# main.net
KiCad netlist of a schematic drawn in EAGLE
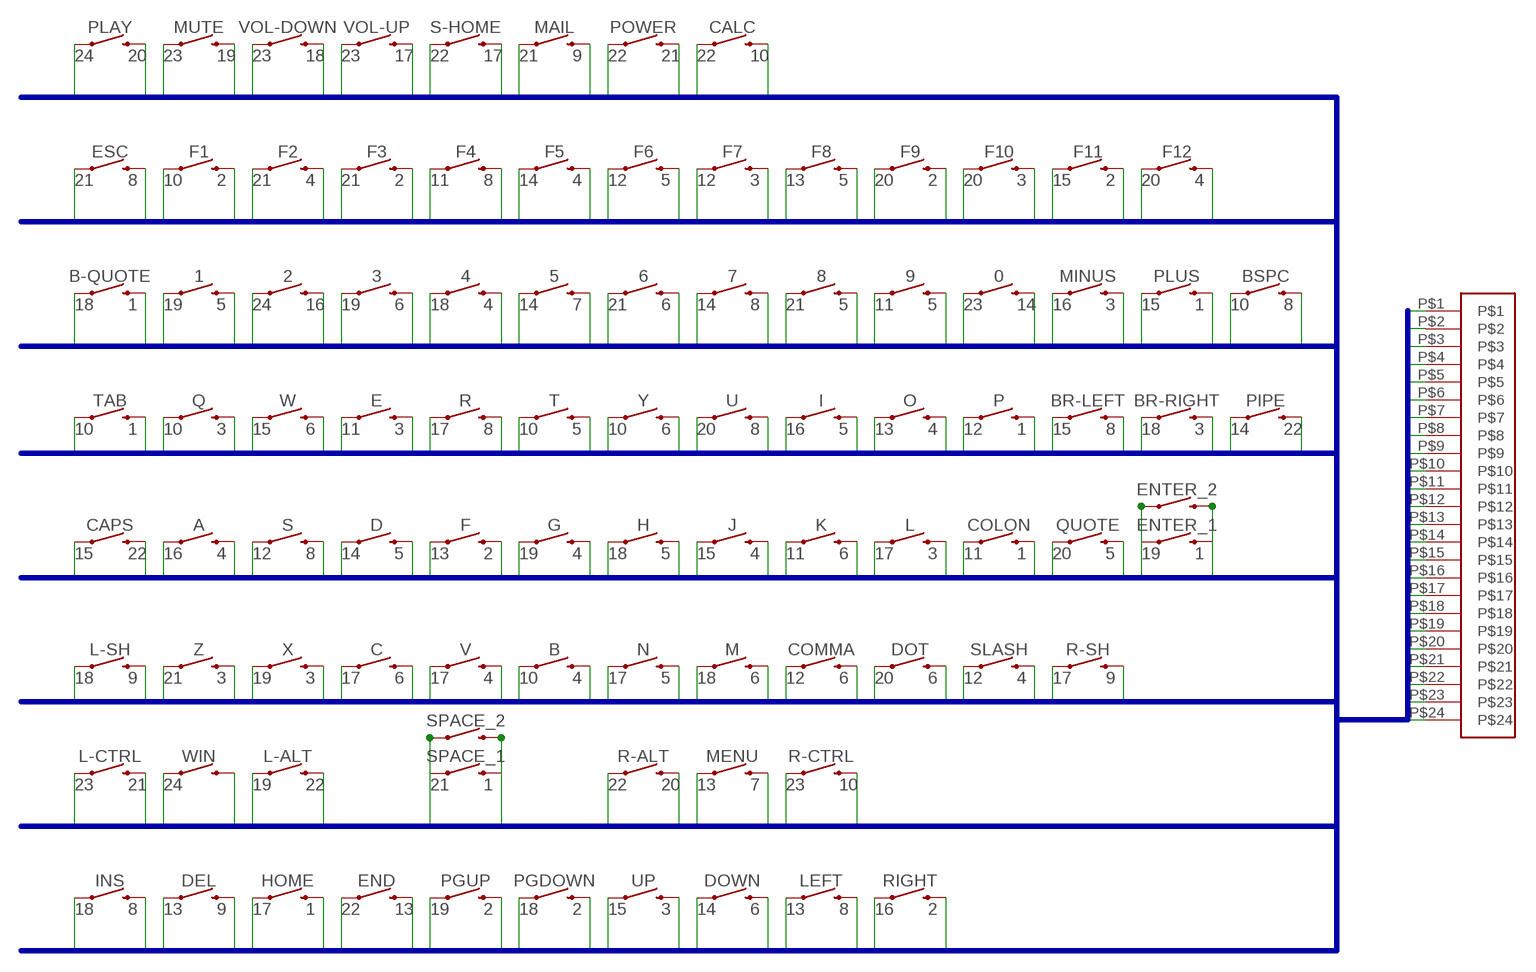
[diagram p0: schematic, sheet 1]

(export (version "E")
  (design (tool "Eeschema 10.0.6"))
  (components
    (comp (ref "0")
      (value "MOMENTARY-SWITCH-SPST-SMD-5.2MM-TALL")
      (footprint "eagle-import:TACTILE_SWITCH_SMD_5.2MM")
      (libsource (lib "eagle-import") (part "MOMENTARY-SWITCH-SPST-SMD-5.2MM-TALL"))
    )
    (comp (ref "1")
      (value "MOMENTARY-SWITCH-SPST-SMD-5.2MM-TALL")
      (footprint "eagle-import:TACTILE_SWITCH_SMD_5.2MM")
      (libsource (lib "eagle-import") (part "MOMENTARY-SWITCH-SPST-SMD-5.2MM-TALL"))
    )
    (comp (ref "2")
      (value "MOMENTARY-SWITCH-SPST-SMD-5.2MM-TALL")
      (footprint "eagle-import:TACTILE_SWITCH_SMD_5.2MM")
      (libsource (lib "eagle-import") (part "MOMENTARY-SWITCH-SPST-SMD-5.2MM-TALL"))
    )
    (comp (ref "3")
      (value "MOMENTARY-SWITCH-SPST-SMD-5.2MM-TALL")
      (footprint "eagle-import:TACTILE_SWITCH_SMD_5.2MM")
      (libsource (lib "eagle-import") (part "MOMENTARY-SWITCH-SPST-SMD-5.2MM-TALL"))
    )
    (comp (ref "4")
      (value "MOMENTARY-SWITCH-SPST-SMD-5.2MM-TALL")
      (footprint "eagle-import:TACTILE_SWITCH_SMD_5.2MM")
      (libsource (lib "eagle-import") (part "MOMENTARY-SWITCH-SPST-SMD-5.2MM-TALL"))
    )
    (comp (ref "5")
      (value "MOMENTARY-SWITCH-SPST-SMD-5.2MM-TALL")
      (footprint "eagle-import:TACTILE_SWITCH_SMD_5.2MM")
      (libsource (lib "eagle-import") (part "MOMENTARY-SWITCH-SPST-SMD-5.2MM-TALL"))
    )
    (comp (ref "6")
      (value "MOMENTARY-SWITCH-SPST-SMD-5.2MM-TALL")
      (footprint "eagle-import:TACTILE_SWITCH_SMD_5.2MM")
      (libsource (lib "eagle-import") (part "MOMENTARY-SWITCH-SPST-SMD-5.2MM-TALL"))
    )
    (comp (ref "7")
      (value "MOMENTARY-SWITCH-SPST-SMD-5.2MM-TALL")
      (footprint "eagle-import:TACTILE_SWITCH_SMD_5.2MM")
      (libsource (lib "eagle-import") (part "MOMENTARY-SWITCH-SPST-SMD-5.2MM-TALL"))
    )
    (comp (ref "8")
      (value "MOMENTARY-SWITCH-SPST-SMD-5.2MM-TALL")
      (footprint "eagle-import:TACTILE_SWITCH_SMD_5.2MM")
      (libsource (lib "eagle-import") (part "MOMENTARY-SWITCH-SPST-SMD-5.2MM-TALL"))
    )
    (comp (ref "9")
      (value "MOMENTARY-SWITCH-SPST-SMD-5.2MM-TALL")
      (footprint "eagle-import:TACTILE_SWITCH_SMD_5.2MM")
      (libsource (lib "eagle-import") (part "MOMENTARY-SWITCH-SPST-SMD-5.2MM-TALL"))
    )
    (comp (ref "A")
      (value "MOMENTARY-SWITCH-SPST-SMD-5.2MM-TALL")
      (footprint "eagle-import:TACTILE_SWITCH_SMD_5.2MM")
      (libsource (lib "eagle-import") (part "MOMENTARY-SWITCH-SPST-SMD-5.2MM-TALL"))
    )
    (comp (ref "B")
      (value "MOMENTARY-SWITCH-SPST-SMD-5.2MM-TALL")
      (footprint "eagle-import:TACTILE_SWITCH_SMD_5.2MM")
      (libsource (lib "eagle-import") (part "MOMENTARY-SWITCH-SPST-SMD-5.2MM-TALL"))
    )
    (comp (ref "B-QUOTE")
      (value "MOMENTARY-SWITCH-SPST-SMD-5.2MM-TALL")
      (footprint "eagle-import:TACTILE_SWITCH_SMD_5.2MM")
      (libsource (lib "eagle-import") (part "MOMENTARY-SWITCH-SPST-SMD-5.2MM-TALL"))
    )
    (comp (ref "BR-LEFT")
      (value "MOMENTARY-SWITCH-SPST-SMD-5.2MM-TALL")
      (footprint "eagle-import:TACTILE_SWITCH_SMD_5.2MM")
      (libsource (lib "eagle-import") (part "MOMENTARY-SWITCH-SPST-SMD-5.2MM-TALL"))
    )
    (comp (ref "BR-RIGHT")
      (value "MOMENTARY-SWITCH-SPST-SMD-5.2MM-TALL")
      (footprint "eagle-import:TACTILE_SWITCH_SMD_5.2MM")
      (libsource (lib "eagle-import") (part "MOMENTARY-SWITCH-SPST-SMD-5.2MM-TALL"))
    )
    (comp (ref "BSPC")
      (value "MOMENTARY-SWITCH-SPST-SMD-5.2MM-TALL")
      (footprint "eagle-import:TACTILE_SWITCH_SMD_5.2MM")
      (libsource (lib "eagle-import") (part "MOMENTARY-SWITCH-SPST-SMD-5.2MM-TALL"))
    )
    (comp (ref "C")
      (value "MOMENTARY-SWITCH-SPST-SMD-5.2MM-TALL")
      (footprint "eagle-import:TACTILE_SWITCH_SMD_5.2MM")
      (libsource (lib "eagle-import") (part "MOMENTARY-SWITCH-SPST-SMD-5.2MM-TALL"))
    )
    (comp (ref "CALC")
      (value "MOMENTARY-SWITCH-SPST-SMD-5.2MM-TALL")
      (footprint "eagle-import:TACTILE_SWITCH_SMD_5.2MM")
      (libsource (lib "eagle-import") (part "MOMENTARY-SWITCH-SPST-SMD-5.2MM-TALL"))
    )
    (comp (ref "CAPS")
      (value "MOMENTARY-SWITCH-SPST-SMD-5.2MM-TALL")
      (footprint "eagle-import:TACTILE_SWITCH_SMD_5.2MM")
      (libsource (lib "eagle-import") (part "MOMENTARY-SWITCH-SPST-SMD-5.2MM-TALL"))
    )
    (comp (ref "COLON")
      (value "MOMENTARY-SWITCH-SPST-SMD-5.2MM-TALL")
      (footprint "eagle-import:TACTILE_SWITCH_SMD_5.2MM")
      (libsource (lib "eagle-import") (part "MOMENTARY-SWITCH-SPST-SMD-5.2MM-TALL"))
    )
    (comp (ref "COMMA")
      (value "MOMENTARY-SWITCH-SPST-SMD-5.2MM-TALL")
      (footprint "eagle-import:TACTILE_SWITCH_SMD_5.2MM")
      (libsource (lib "eagle-import") (part "MOMENTARY-SWITCH-SPST-SMD-5.2MM-TALL"))
    )
    (comp (ref "D")
      (value "MOMENTARY-SWITCH-SPST-SMD-5.2MM-TALL")
      (footprint "eagle-import:TACTILE_SWITCH_SMD_5.2MM")
      (libsource (lib "eagle-import") (part "MOMENTARY-SWITCH-SPST-SMD-5.2MM-TALL"))
    )
    (comp (ref "DEL")
      (value "MOMENTARY-SWITCH-SPST-SMD-5.2MM-TALL")
      (footprint "eagle-import:TACTILE_SWITCH_SMD_5.2MM")
      (libsource (lib "eagle-import") (part "MOMENTARY-SWITCH-SPST-SMD-5.2MM-TALL"))
    )
    (comp (ref "DOT")
      (value "MOMENTARY-SWITCH-SPST-SMD-5.2MM-TALL")
      (footprint "eagle-import:TACTILE_SWITCH_SMD_5.2MM")
      (libsource (lib "eagle-import") (part "MOMENTARY-SWITCH-SPST-SMD-5.2MM-TALL"))
    )
    (comp (ref "DOWN")
      (value "MOMENTARY-SWITCH-SPST-SMD-5.2MM-TALL")
      (footprint "eagle-import:TACTILE_SWITCH_SMD_5.2MM")
      (libsource (lib "eagle-import") (part "MOMENTARY-SWITCH-SPST-SMD-5.2MM-TALL"))
    )
    (comp (ref "E")
      (value "MOMENTARY-SWITCH-SPST-SMD-5.2MM-TALL")
      (footprint "eagle-import:TACTILE_SWITCH_SMD_5.2MM")
      (libsource (lib "eagle-import") (part "MOMENTARY-SWITCH-SPST-SMD-5.2MM-TALL"))
    )
    (comp (ref "END")
      (value "MOMENTARY-SWITCH-SPST-SMD-5.2MM-TALL")
      (footprint "eagle-import:TACTILE_SWITCH_SMD_5.2MM")
      (libsource (lib "eagle-import") (part "MOMENTARY-SWITCH-SPST-SMD-5.2MM-TALL"))
    )
    (comp (ref "ENTER_1")
      (value "MOMENTARY-SWITCH-SPST-SMD-5.2MM-TALL")
      (footprint "eagle-import:TACTILE_SWITCH_SMD_5.2MM")
      (libsource (lib "eagle-import") (part "MOMENTARY-SWITCH-SPST-SMD-5.2MM-TALL"))
    )
    (comp (ref "ENTER_2")
      (value "MOMENTARY-SWITCH-SPST-SMD-5.2MM-TALL")
      (footprint "eagle-import:TACTILE_SWITCH_SMD_5.2MM")
      (libsource (lib "eagle-import") (part "MOMENTARY-SWITCH-SPST-SMD-5.2MM-TALL"))
    )
    (comp (ref "ESC")
      (value "MOMENTARY-SWITCH-SPST-SMD-5.2MM-TALL")
      (footprint "eagle-import:TACTILE_SWITCH_SMD_5.2MM")
      (libsource (lib "eagle-import") (part "MOMENTARY-SWITCH-SPST-SMD-5.2MM-TALL"))
    )
    (comp (ref "F")
      (value "MOMENTARY-SWITCH-SPST-SMD-5.2MM-TALL")
      (footprint "eagle-import:TACTILE_SWITCH_SMD_5.2MM")
      (libsource (lib "eagle-import") (part "MOMENTARY-SWITCH-SPST-SMD-5.2MM-TALL"))
    )
    (comp (ref "F1")
      (value "MOMENTARY-SWITCH-SPST-SMD-5.2MM-TALL")
      (footprint "eagle-import:TACTILE_SWITCH_SMD_5.2MM")
      (libsource (lib "eagle-import") (part "MOMENTARY-SWITCH-SPST-SMD-5.2MM-TALL"))
    )
    (comp (ref "F2")
      (value "MOMENTARY-SWITCH-SPST-SMD-5.2MM-TALL")
      (footprint "eagle-import:TACTILE_SWITCH_SMD_5.2MM")
      (libsource (lib "eagle-import") (part "MOMENTARY-SWITCH-SPST-SMD-5.2MM-TALL"))
    )
    (comp (ref "F3")
      (value "MOMENTARY-SWITCH-SPST-SMD-5.2MM-TALL")
      (footprint "eagle-import:TACTILE_SWITCH_SMD_5.2MM")
      (libsource (lib "eagle-import") (part "MOMENTARY-SWITCH-SPST-SMD-5.2MM-TALL"))
    )
    (comp (ref "F4")
      (value "MOMENTARY-SWITCH-SPST-SMD-5.2MM-TALL")
      (footprint "eagle-import:TACTILE_SWITCH_SMD_5.2MM")
      (libsource (lib "eagle-import") (part "MOMENTARY-SWITCH-SPST-SMD-5.2MM-TALL"))
    )
    (comp (ref "F5")
      (value "MOMENTARY-SWITCH-SPST-SMD-5.2MM-TALL")
      (footprint "eagle-import:TACTILE_SWITCH_SMD_5.2MM")
      (libsource (lib "eagle-import") (part "MOMENTARY-SWITCH-SPST-SMD-5.2MM-TALL"))
    )
    (comp (ref "F6")
      (value "MOMENTARY-SWITCH-SPST-SMD-5.2MM-TALL")
      (footprint "eagle-import:TACTILE_SWITCH_SMD_5.2MM")
      (libsource (lib "eagle-import") (part "MOMENTARY-SWITCH-SPST-SMD-5.2MM-TALL"))
    )
    (comp (ref "F7")
      (value "MOMENTARY-SWITCH-SPST-SMD-5.2MM-TALL")
      (footprint "eagle-import:TACTILE_SWITCH_SMD_5.2MM")
      (libsource (lib "eagle-import") (part "MOMENTARY-SWITCH-SPST-SMD-5.2MM-TALL"))
    )
    (comp (ref "F8")
      (value "MOMENTARY-SWITCH-SPST-SMD-5.2MM-TALL")
      (footprint "eagle-import:TACTILE_SWITCH_SMD_5.2MM")
      (libsource (lib "eagle-import") (part "MOMENTARY-SWITCH-SPST-SMD-5.2MM-TALL"))
    )
    (comp (ref "F9")
      (value "MOMENTARY-SWITCH-SPST-SMD-5.2MM-TALL")
      (footprint "eagle-import:TACTILE_SWITCH_SMD_5.2MM")
      (libsource (lib "eagle-import") (part "MOMENTARY-SWITCH-SPST-SMD-5.2MM-TALL"))
    )
    (comp (ref "F10")
      (value "MOMENTARY-SWITCH-SPST-SMD-5.2MM-TALL")
      (footprint "eagle-import:TACTILE_SWITCH_SMD_5.2MM")
      (libsource (lib "eagle-import") (part "MOMENTARY-SWITCH-SPST-SMD-5.2MM-TALL"))
    )
    (comp (ref "F11")
      (value "MOMENTARY-SWITCH-SPST-SMD-5.2MM-TALL")
      (footprint "eagle-import:TACTILE_SWITCH_SMD_5.2MM")
      (libsource (lib "eagle-import") (part "MOMENTARY-SWITCH-SPST-SMD-5.2MM-TALL"))
    )
    (comp (ref "F12")
      (value "MOMENTARY-SWITCH-SPST-SMD-5.2MM-TALL")
      (footprint "eagle-import:TACTILE_SWITCH_SMD_5.2MM")
      (libsource (lib "eagle-import") (part "MOMENTARY-SWITCH-SPST-SMD-5.2MM-TALL"))
    )
    (comp (ref "G")
      (value "MOMENTARY-SWITCH-SPST-SMD-5.2MM-TALL")
      (footprint "eagle-import:TACTILE_SWITCH_SMD_5.2MM")
      (libsource (lib "eagle-import") (part "MOMENTARY-SWITCH-SPST-SMD-5.2MM-TALL"))
    )
    (comp (ref "H")
      (value "MOMENTARY-SWITCH-SPST-SMD-5.2MM-TALL")
      (footprint "eagle-import:TACTILE_SWITCH_SMD_5.2MM")
      (libsource (lib "eagle-import") (part "MOMENTARY-SWITCH-SPST-SMD-5.2MM-TALL"))
    )
    (comp (ref "HOME")
      (value "MOMENTARY-SWITCH-SPST-SMD-5.2MM-TALL")
      (footprint "eagle-import:TACTILE_SWITCH_SMD_5.2MM")
      (libsource (lib "eagle-import") (part "MOMENTARY-SWITCH-SPST-SMD-5.2MM-TALL"))
    )
    (comp (ref "I")
      (value "MOMENTARY-SWITCH-SPST-SMD-5.2MM-TALL")
      (footprint "eagle-import:TACTILE_SWITCH_SMD_5.2MM")
      (libsource (lib "eagle-import") (part "MOMENTARY-SWITCH-SPST-SMD-5.2MM-TALL"))
    )
    (comp (ref "INS")
      (value "MOMENTARY-SWITCH-SPST-SMD-5.2MM-TALL")
      (footprint "eagle-import:TACTILE_SWITCH_SMD_5.2MM")
      (libsource (lib "eagle-import") (part "MOMENTARY-SWITCH-SPST-SMD-5.2MM-TALL"))
    )
    (comp (ref "J")
      (value "MOMENTARY-SWITCH-SPST-SMD-5.2MM-TALL")
      (footprint "eagle-import:TACTILE_SWITCH_SMD_5.2MM")
      (libsource (lib "eagle-import") (part "MOMENTARY-SWITCH-SPST-SMD-5.2MM-TALL"))
    )
    (comp (ref "K")
      (value "MOMENTARY-SWITCH-SPST-SMD-5.2MM-TALL")
      (footprint "eagle-import:TACTILE_SWITCH_SMD_5.2MM")
      (libsource (lib "eagle-import") (part "MOMENTARY-SWITCH-SPST-SMD-5.2MM-TALL"))
    )
    (comp (ref "L")
      (value "MOMENTARY-SWITCH-SPST-SMD-5.2MM-TALL")
      (footprint "eagle-import:TACTILE_SWITCH_SMD_5.2MM")
      (libsource (lib "eagle-import") (part "MOMENTARY-SWITCH-SPST-SMD-5.2MM-TALL"))
    )
    (comp (ref "L-ALT")
      (value "MOMENTARY-SWITCH-SPST-SMD-5.2MM-TALL")
      (footprint "eagle-import:TACTILE_SWITCH_SMD_5.2MM")
      (libsource (lib "eagle-import") (part "MOMENTARY-SWITCH-SPST-SMD-5.2MM-TALL"))
    )
    (comp (ref "L-CTRL")
      (value "MOMENTARY-SWITCH-SPST-SMD-5.2MM-TALL")
      (footprint "eagle-import:TACTILE_SWITCH_SMD_5.2MM")
      (libsource (lib "eagle-import") (part "MOMENTARY-SWITCH-SPST-SMD-5.2MM-TALL"))
    )
    (comp (ref "L-SH")
      (value "MOMENTARY-SWITCH-SPST-SMD-5.2MM-TALL")
      (footprint "eagle-import:TACTILE_SWITCH_SMD_5.2MM")
      (libsource (lib "eagle-import") (part "MOMENTARY-SWITCH-SPST-SMD-5.2MM-TALL"))
    )
    (comp (ref "LEFT")
      (value "MOMENTARY-SWITCH-SPST-SMD-5.2MM-TALL")
      (footprint "eagle-import:TACTILE_SWITCH_SMD_5.2MM")
      (libsource (lib "eagle-import") (part "MOMENTARY-SWITCH-SPST-SMD-5.2MM-TALL"))
    )
    (comp (ref "M")
      (value "MOMENTARY-SWITCH-SPST-SMD-5.2MM-TALL")
      (footprint "eagle-import:TACTILE_SWITCH_SMD_5.2MM")
      (libsource (lib "eagle-import") (part "MOMENTARY-SWITCH-SPST-SMD-5.2MM-TALL"))
    )
    (comp (ref "MAIL")
      (value "MOMENTARY-SWITCH-SPST-SMD-5.2MM-TALL")
      (footprint "eagle-import:TACTILE_SWITCH_SMD_5.2MM")
      (libsource (lib "eagle-import") (part "MOMENTARY-SWITCH-SPST-SMD-5.2MM-TALL"))
    )
    (comp (ref "MENU")
      (value "MOMENTARY-SWITCH-SPST-SMD-5.2MM-TALL")
      (footprint "eagle-import:TACTILE_SWITCH_SMD_5.2MM")
      (libsource (lib "eagle-import") (part "MOMENTARY-SWITCH-SPST-SMD-5.2MM-TALL"))
    )
    (comp (ref "MINUS")
      (value "MOMENTARY-SWITCH-SPST-SMD-5.2MM-TALL")
      (footprint "eagle-import:TACTILE_SWITCH_SMD_5.2MM")
      (libsource (lib "eagle-import") (part "MOMENTARY-SWITCH-SPST-SMD-5.2MM-TALL"))
    )
    (comp (ref "MUTE")
      (value "MOMENTARY-SWITCH-SPST-SMD-5.2MM-TALL")
      (footprint "eagle-import:TACTILE_SWITCH_SMD_5.2MM")
      (libsource (lib "eagle-import") (part "MOMENTARY-SWITCH-SPST-SMD-5.2MM-TALL"))
    )
    (comp (ref "N")
      (value "MOMENTARY-SWITCH-SPST-SMD-5.2MM-TALL")
      (footprint "eagle-import:TACTILE_SWITCH_SMD_5.2MM")
      (libsource (lib "eagle-import") (part "MOMENTARY-SWITCH-SPST-SMD-5.2MM-TALL"))
    )
    (comp (ref "O")
      (value "MOMENTARY-SWITCH-SPST-SMD-5.2MM-TALL")
      (footprint "eagle-import:TACTILE_SWITCH_SMD_5.2MM")
      (libsource (lib "eagle-import") (part "MOMENTARY-SWITCH-SPST-SMD-5.2MM-TALL"))
    )
    (comp (ref "P")
      (value "MOMENTARY-SWITCH-SPST-SMD-5.2MM-TALL")
      (footprint "eagle-import:TACTILE_SWITCH_SMD_5.2MM")
      (libsource (lib "eagle-import") (part "MOMENTARY-SWITCH-SPST-SMD-5.2MM-TALL"))
    )
    (comp (ref "PGDOWN")
      (value "MOMENTARY-SWITCH-SPST-SMD-5.2MM-TALL")
      (footprint "eagle-import:TACTILE_SWITCH_SMD_5.2MM")
      (libsource (lib "eagle-import") (part "MOMENTARY-SWITCH-SPST-SMD-5.2MM-TALL"))
    )
    (comp (ref "PGUP")
      (value "MOMENTARY-SWITCH-SPST-SMD-5.2MM-TALL")
      (footprint "eagle-import:TACTILE_SWITCH_SMD_5.2MM")
      (libsource (lib "eagle-import") (part "MOMENTARY-SWITCH-SPST-SMD-5.2MM-TALL"))
    )
    (comp (ref "PIPE")
      (value "MOMENTARY-SWITCH-SPST-SMD-5.2MM-TALL")
      (footprint "eagle-import:TACTILE_SWITCH_SMD_5.2MM")
      (libsource (lib "eagle-import") (part "MOMENTARY-SWITCH-SPST-SMD-5.2MM-TALL"))
    )
    (comp (ref "PLAY")
      (value "MOMENTARY-SWITCH-SPST-SMD-5.2MM-TALL")
      (footprint "eagle-import:TACTILE_SWITCH_SMD_5.2MM")
      (libsource (lib "eagle-import") (part "MOMENTARY-SWITCH-SPST-SMD-5.2MM-TALL"))
    )
    (comp (ref "PLUS")
      (value "MOMENTARY-SWITCH-SPST-SMD-5.2MM-TALL")
      (footprint "eagle-import:TACTILE_SWITCH_SMD_5.2MM")
      (libsource (lib "eagle-import") (part "MOMENTARY-SWITCH-SPST-SMD-5.2MM-TALL"))
    )
    (comp (ref "POWER")
      (value "MOMENTARY-SWITCH-SPST-SMD-5.2MM-TALL")
      (footprint "eagle-import:TACTILE_SWITCH_SMD_5.2MM")
      (libsource (lib "eagle-import") (part "MOMENTARY-SWITCH-SPST-SMD-5.2MM-TALL"))
    )
    (comp (ref "Q")
      (value "MOMENTARY-SWITCH-SPST-SMD-5.2MM-TALL")
      (footprint "eagle-import:TACTILE_SWITCH_SMD_5.2MM")
      (libsource (lib "eagle-import") (part "MOMENTARY-SWITCH-SPST-SMD-5.2MM-TALL"))
    )
    (comp (ref "QUOTE")
      (value "MOMENTARY-SWITCH-SPST-SMD-5.2MM-TALL")
      (footprint "eagle-import:TACTILE_SWITCH_SMD_5.2MM")
      (libsource (lib "eagle-import") (part "MOMENTARY-SWITCH-SPST-SMD-5.2MM-TALL"))
    )
    (comp (ref "R")
      (value "MOMENTARY-SWITCH-SPST-SMD-5.2MM-TALL")
      (footprint "eagle-import:TACTILE_SWITCH_SMD_5.2MM")
      (libsource (lib "eagle-import") (part "MOMENTARY-SWITCH-SPST-SMD-5.2MM-TALL"))
    )
    (comp (ref "R-ALT")
      (value "MOMENTARY-SWITCH-SPST-SMD-5.2MM-TALL")
      (footprint "eagle-import:TACTILE_SWITCH_SMD_5.2MM")
      (libsource (lib "eagle-import") (part "MOMENTARY-SWITCH-SPST-SMD-5.2MM-TALL"))
    )
    (comp (ref "R-CTRL")
      (value "MOMENTARY-SWITCH-SPST-SMD-5.2MM-TALL")
      (footprint "eagle-import:TACTILE_SWITCH_SMD_5.2MM")
      (libsource (lib "eagle-import") (part "MOMENTARY-SWITCH-SPST-SMD-5.2MM-TALL"))
    )
    (comp (ref "R-SH")
      (value "MOMENTARY-SWITCH-SPST-SMD-5.2MM-TALL")
      (footprint "eagle-import:TACTILE_SWITCH_SMD_5.2MM")
      (libsource (lib "eagle-import") (part "MOMENTARY-SWITCH-SPST-SMD-5.2MM-TALL"))
    )
    (comp (ref "RIGHT")
      (value "MOMENTARY-SWITCH-SPST-SMD-5.2MM-TALL")
      (footprint "eagle-import:TACTILE_SWITCH_SMD_5.2MM")
      (libsource (lib "eagle-import") (part "MOMENTARY-SWITCH-SPST-SMD-5.2MM-TALL"))
    )
    (comp (ref "S")
      (value "MOMENTARY-SWITCH-SPST-SMD-5.2MM-TALL")
      (footprint "eagle-import:TACTILE_SWITCH_SMD_5.2MM")
      (libsource (lib "eagle-import") (part "MOMENTARY-SWITCH-SPST-SMD-5.2MM-TALL"))
    )
    (comp (ref "S-HOME")
      (value "MOMENTARY-SWITCH-SPST-SMD-5.2MM-TALL")
      (footprint "eagle-import:TACTILE_SWITCH_SMD_5.2MM")
      (libsource (lib "eagle-import") (part "MOMENTARY-SWITCH-SPST-SMD-5.2MM-TALL"))
    )
    (comp (ref "SLASH")
      (value "MOMENTARY-SWITCH-SPST-SMD-5.2MM-TALL")
      (footprint "eagle-import:TACTILE_SWITCH_SMD_5.2MM")
      (libsource (lib "eagle-import") (part "MOMENTARY-SWITCH-SPST-SMD-5.2MM-TALL"))
    )
    (comp (ref "SPACE_1")
      (value "MOMENTARY-SWITCH-SPST-SMD-5.2MM-TALL")
      (footprint "eagle-import:TACTILE_SWITCH_SMD_5.2MM")
      (libsource (lib "eagle-import") (part "MOMENTARY-SWITCH-SPST-SMD-5.2MM-TALL"))
    )
    (comp (ref "SPACE_2")
      (value "MOMENTARY-SWITCH-SPST-SMD-5.2MM-TALL")
      (footprint "eagle-import:TACTILE_SWITCH_SMD_5.2MM")
      (libsource (lib "eagle-import") (part "MOMENTARY-SWITCH-SPST-SMD-5.2MM-TALL"))
    )
    (comp (ref "T")
      (value "MOMENTARY-SWITCH-SPST-SMD-5.2MM-TALL")
      (footprint "eagle-import:TACTILE_SWITCH_SMD_5.2MM")
      (libsource (lib "eagle-import") (part "MOMENTARY-SWITCH-SPST-SMD-5.2MM-TALL"))
    )
    (comp (ref "TAB")
      (value "MOMENTARY-SWITCH-SPST-SMD-5.2MM-TALL")
      (footprint "eagle-import:TACTILE_SWITCH_SMD_5.2MM")
      (libsource (lib "eagle-import") (part "MOMENTARY-SWITCH-SPST-SMD-5.2MM-TALL"))
    )
    (comp (ref "U")
      (value "MOMENTARY-SWITCH-SPST-SMD-5.2MM-TALL")
      (footprint "eagle-import:TACTILE_SWITCH_SMD_5.2MM")
      (libsource (lib "eagle-import") (part "MOMENTARY-SWITCH-SPST-SMD-5.2MM-TALL"))
    )
    (comp (ref "U$1")
      (value "LOGITECH_KBD_24_PIN_CONNECTOR")
      (footprint "eagle-import:LOGITECH_KBD_24_PIN_CONNECTOR")
      (libsource (lib "eagle-import") (part "LOGITECH_KBD_24_PIN_CONNECTOR"))
    )
    (comp (ref "UP")
      (value "MOMENTARY-SWITCH-SPST-SMD-5.2MM-TALL")
      (footprint "eagle-import:TACTILE_SWITCH_SMD_5.2MM")
      (libsource (lib "eagle-import") (part "MOMENTARY-SWITCH-SPST-SMD-5.2MM-TALL"))
    )
    (comp (ref "V")
      (value "MOMENTARY-SWITCH-SPST-SMD-5.2MM-TALL")
      (footprint "eagle-import:TACTILE_SWITCH_SMD_5.2MM")
      (libsource (lib "eagle-import") (part "MOMENTARY-SWITCH-SPST-SMD-5.2MM-TALL"))
    )
    (comp (ref "VOL-DOWN")
      (value "MOMENTARY-SWITCH-SPST-SMD-5.2MM-TALL")
      (footprint "eagle-import:TACTILE_SWITCH_SMD_5.2MM")
      (libsource (lib "eagle-import") (part "MOMENTARY-SWITCH-SPST-SMD-5.2MM-TALL"))
    )
    (comp (ref "VOL-UP")
      (value "MOMENTARY-SWITCH-SPST-SMD-5.2MM-TALL")
      (footprint "eagle-import:TACTILE_SWITCH_SMD_5.2MM")
      (libsource (lib "eagle-import") (part "MOMENTARY-SWITCH-SPST-SMD-5.2MM-TALL"))
    )
    (comp (ref "W")
      (value "MOMENTARY-SWITCH-SPST-SMD-5.2MM-TALL")
      (footprint "eagle-import:TACTILE_SWITCH_SMD_5.2MM")
      (libsource (lib "eagle-import") (part "MOMENTARY-SWITCH-SPST-SMD-5.2MM-TALL"))
    )
    (comp (ref "WIN")
      (value "MOMENTARY-SWITCH-SPST-SMD-5.2MM-TALL")
      (footprint "eagle-import:TACTILE_SWITCH_SMD_5.2MM")
      (libsource (lib "eagle-import") (part "MOMENTARY-SWITCH-SPST-SMD-5.2MM-TALL"))
    )
    (comp (ref "X")
      (value "MOMENTARY-SWITCH-SPST-SMD-5.2MM-TALL")
      (footprint "eagle-import:TACTILE_SWITCH_SMD_5.2MM")
      (libsource (lib "eagle-import") (part "MOMENTARY-SWITCH-SPST-SMD-5.2MM-TALL"))
    )
    (comp (ref "Y")
      (value "MOMENTARY-SWITCH-SPST-SMD-5.2MM-TALL")
      (footprint "eagle-import:TACTILE_SWITCH_SMD_5.2MM")
      (libsource (lib "eagle-import") (part "MOMENTARY-SWITCH-SPST-SMD-5.2MM-TALL"))
    )
    (comp (ref "Z")
      (value "MOMENTARY-SWITCH-SPST-SMD-5.2MM-TALL")
      (footprint "eagle-import:TACTILE_SWITCH_SMD_5.2MM")
      (libsource (lib "eagle-import") (part "MOMENTARY-SWITCH-SPST-SMD-5.2MM-TALL"))
    )
  )
  (nets
    (net (code "1") (name "/1") (class "Default")
      (node (ref "B-QUOTE") (pin "3") (pinfunction "2_3") (pintype "passive"))
      (node (ref "COLON") (pin "3") (pinfunction "2_3") (pintype "passive"))
      (node (ref "ENTER_1") (pin "3") (pinfunction "2_3") (pintype "passive"))
      (node (ref "ENTER_2") (pin "3") (pinfunction "2_3") (pintype "passive"))
      (node (ref "HOME") (pin "3") (pinfunction "2_3") (pintype "passive"))
      (node (ref "P") (pin "3") (pinfunction "2_3") (pintype "passive"))
      (node (ref "PLUS") (pin "3") (pinfunction "2_3") (pintype "passive"))
      (node (ref "SPACE_1") (pin "3") (pinfunction "2_3") (pintype "passive"))
      (node (ref "SPACE_2") (pin "3") (pinfunction "2_3") (pintype "passive"))
      (node (ref "TAB") (pin "3") (pinfunction "2_3") (pintype "passive"))
      (node (ref "U$1") (pin "P$1") (pinfunction "P$1_P$1") (pintype "bidirectional"))
    )
    (net (code "2") (name "/2") (class "Default")
      (node (ref "F") (pin "3") (pinfunction "2_3") (pintype "passive"))
      (node (ref "F1") (pin "3") (pinfunction "2_3") (pintype "passive"))
      (node (ref "F11") (pin "3") (pinfunction "2_3") (pintype "passive"))
      (node (ref "F3") (pin "3") (pinfunction "2_3") (pintype "passive"))
      (node (ref "F9") (pin "3") (pinfunction "2_3") (pintype "passive"))
      (node (ref "PGDOWN") (pin "3") (pinfunction "2_3") (pintype "passive"))
      (node (ref "PGUP") (pin "3") (pinfunction "2_3") (pintype "passive"))
      (node (ref "RIGHT") (pin "3") (pinfunction "2_3") (pintype "passive"))
      (node (ref "U$1") (pin "P$2") (pinfunction "P$2_P$2") (pintype "bidirectional"))
    )
    (net (code "3") (name "/3") (class "Default")
      (node (ref "BR-RIGHT") (pin "3") (pinfunction "2_3") (pintype "passive"))
      (node (ref "E") (pin "3") (pinfunction "2_3") (pintype "passive"))
      (node (ref "F10") (pin "3") (pinfunction "2_3") (pintype "passive"))
      (node (ref "F7") (pin "3") (pinfunction "2_3") (pintype "passive"))
      (node (ref "L") (pin "3") (pinfunction "2_3") (pintype "passive"))
      (node (ref "MINUS") (pin "3") (pinfunction "2_3") (pintype "passive"))
      (node (ref "Q") (pin "3") (pinfunction "2_3") (pintype "passive"))
      (node (ref "U$1") (pin "P$3") (pinfunction "P$3_P$3") (pintype "bidirectional"))
      (node (ref "UP") (pin "3") (pinfunction "2_3") (pintype "passive"))
      (node (ref "X") (pin "3") (pinfunction "2_3") (pintype "passive"))
      (node (ref "Z") (pin "3") (pinfunction "2_3") (pintype "passive"))
    )
    (net (code "4") (name "/4") (class "Default")
      (node (ref "4") (pin "3") (pinfunction "2_3") (pintype "passive"))
      (node (ref "A") (pin "3") (pinfunction "2_3") (pintype "passive"))
      (node (ref "B") (pin "3") (pinfunction "2_3") (pintype "passive"))
      (node (ref "F12") (pin "3") (pinfunction "2_3") (pintype "passive"))
      (node (ref "F2") (pin "3") (pinfunction "2_3") (pintype "passive"))
      (node (ref "F5") (pin "3") (pinfunction "2_3") (pintype "passive"))
      (node (ref "G") (pin "3") (pinfunction "2_3") (pintype "passive"))
      (node (ref "J") (pin "3") (pinfunction "2_3") (pintype "passive"))
      (node (ref "O") (pin "3") (pinfunction "2_3") (pintype "passive"))
      (node (ref "SLASH") (pin "3") (pinfunction "2_3") (pintype "passive"))
      (node (ref "U$1") (pin "P$4") (pinfunction "P$4_P$4") (pintype "bidirectional"))
      (node (ref "V") (pin "3") (pinfunction "2_3") (pintype "passive"))
    )
    (net (code "5") (name "/5") (class "Default")
      (node (ref "1") (pin "3") (pinfunction "2_3") (pintype "passive"))
      (node (ref "8") (pin "3") (pinfunction "2_3") (pintype "passive"))
      (node (ref "9") (pin "3") (pinfunction "2_3") (pintype "passive"))
      (node (ref "D") (pin "3") (pinfunction "2_3") (pintype "passive"))
      (node (ref "F6") (pin "3") (pinfunction "2_3") (pintype "passive"))
      (node (ref "F8") (pin "3") (pinfunction "2_3") (pintype "passive"))
      (node (ref "H") (pin "3") (pinfunction "2_3") (pintype "passive"))
      (node (ref "I") (pin "3") (pinfunction "2_3") (pintype "passive"))
      (node (ref "N") (pin "3") (pinfunction "2_3") (pintype "passive"))
      (node (ref "QUOTE") (pin "3") (pinfunction "2_3") (pintype "passive"))
      (node (ref "T") (pin "3") (pinfunction "2_3") (pintype "passive"))
      (node (ref "U$1") (pin "P$5") (pinfunction "P$5_P$5") (pintype "bidirectional"))
    )
    (net (code "6") (name "/6") (class "Default")
      (node (ref "3") (pin "3") (pinfunction "2_3") (pintype "passive"))
      (node (ref "6") (pin "3") (pinfunction "2_3") (pintype "passive"))
      (node (ref "C") (pin "3") (pinfunction "2_3") (pintype "passive"))
      (node (ref "COMMA") (pin "3") (pinfunction "2_3") (pintype "passive"))
      (node (ref "DOT") (pin "3") (pinfunction "2_3") (pintype "passive"))
      (node (ref "DOWN") (pin "3") (pinfunction "2_3") (pintype "passive"))
      (node (ref "K") (pin "3") (pinfunction "2_3") (pintype "passive"))
      (node (ref "M") (pin "3") (pinfunction "2_3") (pintype "passive"))
      (node (ref "U$1") (pin "P$6") (pinfunction "P$6_P$6") (pintype "bidirectional"))
      (node (ref "W") (pin "3") (pinfunction "2_3") (pintype "passive"))
      (node (ref "Y") (pin "3") (pinfunction "2_3") (pintype "passive"))
    )
    (net (code "7") (name "/7") (class "Default")
      (node (ref "5") (pin "3") (pinfunction "2_3") (pintype "passive"))
      (node (ref "MENU") (pin "3") (pinfunction "2_3") (pintype "passive"))
      (node (ref "U$1") (pin "P$7") (pinfunction "P$7_P$7") (pintype "bidirectional"))
    )
    (net (code "8") (name "/8") (class "Default")
      (node (ref "7") (pin "3") (pinfunction "2_3") (pintype "passive"))
      (node (ref "BR-LEFT") (pin "3") (pinfunction "2_3") (pintype "passive"))
      (node (ref "BSPC") (pin "3") (pinfunction "2_3") (pintype "passive"))
      (node (ref "ESC") (pin "3") (pinfunction "2_3") (pintype "passive"))
      (node (ref "F4") (pin "3") (pinfunction "2_3") (pintype "passive"))
      (node (ref "INS") (pin "3") (pinfunction "2_3") (pintype "passive"))
      (node (ref "LEFT") (pin "3") (pinfunction "2_3") (pintype "passive"))
      (node (ref "R") (pin "3") (pinfunction "2_3") (pintype "passive"))
      (node (ref "S") (pin "3") (pinfunction "2_3") (pintype "passive"))
      (node (ref "U") (pin "3") (pinfunction "2_3") (pintype "passive"))
      (node (ref "U$1") (pin "P$8") (pinfunction "P$8_P$8") (pintype "bidirectional"))
    )
    (net (code "9") (name "/9") (class "Default")
      (node (ref "DEL") (pin "3") (pinfunction "2_3") (pintype "passive"))
      (node (ref "L-SH") (pin "3") (pinfunction "2_3") (pintype "passive"))
      (node (ref "MAIL") (pin "3") (pinfunction "2_3") (pintype "passive"))
      (node (ref "R-SH") (pin "3") (pinfunction "2_3") (pintype "passive"))
      (node (ref "U$1") (pin "P$9") (pinfunction "P$9_P$9") (pintype "bidirectional"))
    )
    (net (code "10") (name "/10") (class "Default")
      (node (ref "B") (pin "1") (pinfunction "1_1") (pintype "passive"))
      (node (ref "BSPC") (pin "1") (pinfunction "1_1") (pintype "passive"))
      (node (ref "CALC") (pin "3") (pinfunction "2_3") (pintype "passive"))
      (node (ref "F1") (pin "1") (pinfunction "1_1") (pintype "passive"))
      (node (ref "Q") (pin "1") (pinfunction "1_1") (pintype "passive"))
      (node (ref "R-CTRL") (pin "3") (pinfunction "2_3") (pintype "passive"))
      (node (ref "T") (pin "1") (pinfunction "1_1") (pintype "passive"))
      (node (ref "TAB") (pin "1") (pinfunction "1_1") (pintype "passive"))
      (node (ref "U$1") (pin "P$10") (pinfunction "P$10_P$10") (pintype "bidirectional"))
      (node (ref "Y") (pin "1") (pinfunction "1_1") (pintype "passive"))
    )
    (net (code "11") (name "/11") (class "Default")
      (node (ref "9") (pin "1") (pinfunction "1_1") (pintype "passive"))
      (node (ref "COLON") (pin "1") (pinfunction "1_1") (pintype "passive"))
      (node (ref "E") (pin "1") (pinfunction "1_1") (pintype "passive"))
      (node (ref "F4") (pin "1") (pinfunction "1_1") (pintype "passive"))
      (node (ref "K") (pin "1") (pinfunction "1_1") (pintype "passive"))
      (node (ref "U$1") (pin "P$11") (pinfunction "P$11_P$11") (pintype "bidirectional"))
      (node (ref "WIN") (pin "3") (pinfunction "2_3") (pintype "passive"))
    )
    (net (code "12") (name "/12") (class "Default")
      (node (ref "COMMA") (pin "1") (pinfunction "1_1") (pintype "passive"))
      (node (ref "F6") (pin "1") (pinfunction "1_1") (pintype "passive"))
      (node (ref "F7") (pin "1") (pinfunction "1_1") (pintype "passive"))
      (node (ref "P") (pin "1") (pinfunction "1_1") (pintype "passive"))
      (node (ref "S") (pin "1") (pinfunction "1_1") (pintype "passive"))
      (node (ref "SLASH") (pin "1") (pinfunction "1_1") (pintype "passive"))
      (node (ref "U$1") (pin "P$12") (pinfunction "P$12_P$12") (pintype "bidirectional"))
    )
    (net (code "13") (name "/13") (class "Default")
      (node (ref "DEL") (pin "1") (pinfunction "1_1") (pintype "passive"))
      (node (ref "END") (pin "3") (pinfunction "2_3") (pintype "passive"))
      (node (ref "F") (pin "1") (pinfunction "1_1") (pintype "passive"))
      (node (ref "F8") (pin "1") (pinfunction "1_1") (pintype "passive"))
      (node (ref "LEFT") (pin "1") (pinfunction "1_1") (pintype "passive"))
      (node (ref "MENU") (pin "1") (pinfunction "1_1") (pintype "passive"))
      (node (ref "O") (pin "1") (pinfunction "1_1") (pintype "passive"))
      (node (ref "U$1") (pin "P$13") (pinfunction "P$13_P$13") (pintype "bidirectional"))
    )
    (net (code "14") (name "/14") (class "Default")
      (node (ref "0") (pin "3") (pinfunction "2_3") (pintype "passive"))
      (node (ref "5") (pin "1") (pinfunction "1_1") (pintype "passive"))
      (node (ref "7") (pin "1") (pinfunction "1_1") (pintype "passive"))
      (node (ref "D") (pin "1") (pinfunction "1_1") (pintype "passive"))
      (node (ref "DOWN") (pin "1") (pinfunction "1_1") (pintype "passive"))
      (node (ref "F5") (pin "1") (pinfunction "1_1") (pintype "passive"))
      (node (ref "PIPE") (pin "1") (pinfunction "1_1") (pintype "passive"))
      (node (ref "U$1") (pin "P$14") (pinfunction "P$14_P$14") (pintype "bidirectional"))
    )
    (net (code "15") (name "/15") (class "Default")
      (node (ref "BR-LEFT") (pin "1") (pinfunction "1_1") (pintype "passive"))
      (node (ref "CAPS") (pin "1") (pinfunction "1_1") (pintype "passive"))
      (node (ref "F11") (pin "1") (pinfunction "1_1") (pintype "passive"))
      (node (ref "J") (pin "1") (pinfunction "1_1") (pintype "passive"))
      (node (ref "PLUS") (pin "1") (pinfunction "1_1") (pintype "passive"))
      (node (ref "U$1") (pin "P$15") (pinfunction "P$15_P$15") (pintype "bidirectional"))
      (node (ref "UP") (pin "1") (pinfunction "1_1") (pintype "passive"))
      (node (ref "W") (pin "1") (pinfunction "1_1") (pintype "passive"))
    )
    (net (code "16") (name "/16") (class "Default")
      (node (ref "2") (pin "3") (pinfunction "2_3") (pintype "passive"))
      (node (ref "A") (pin "1") (pinfunction "1_1") (pintype "passive"))
      (node (ref "I") (pin "1") (pinfunction "1_1") (pintype "passive"))
      (node (ref "MINUS") (pin "1") (pinfunction "1_1") (pintype "passive"))
      (node (ref "RIGHT") (pin "1") (pinfunction "1_1") (pintype "passive"))
      (node (ref "U$1") (pin "P$16") (pinfunction "P$16_P$16") (pintype "bidirectional"))
    )
    (net (code "17") (name "/17") (class "Default")
      (node (ref "C") (pin "1") (pinfunction "1_1") (pintype "passive"))
      (node (ref "HOME") (pin "1") (pinfunction "1_1") (pintype "passive"))
      (node (ref "L") (pin "1") (pinfunction "1_1") (pintype "passive"))
      (node (ref "N") (pin "1") (pinfunction "1_1") (pintype "passive"))
      (node (ref "R") (pin "1") (pinfunction "1_1") (pintype "passive"))
      (node (ref "R-SH") (pin "1") (pinfunction "1_1") (pintype "passive"))
      (node (ref "S-HOME") (pin "3") (pinfunction "2_3") (pintype "passive"))
      (node (ref "U$1") (pin "P$17") (pinfunction "P$17_P$17") (pintype "bidirectional"))
      (node (ref "V") (pin "1") (pinfunction "1_1") (pintype "passive"))
      (node (ref "VOL-UP") (pin "3") (pinfunction "2_3") (pintype "passive"))
    )
    (net (code "18") (name "/18") (class "Default")
      (node (ref "4") (pin "1") (pinfunction "1_1") (pintype "passive"))
      (node (ref "B-QUOTE") (pin "1") (pinfunction "1_1") (pintype "passive"))
      (node (ref "BR-RIGHT") (pin "1") (pinfunction "1_1") (pintype "passive"))
      (node (ref "H") (pin "1") (pinfunction "1_1") (pintype "passive"))
      (node (ref "INS") (pin "1") (pinfunction "1_1") (pintype "passive"))
      (node (ref "L-SH") (pin "1") (pinfunction "1_1") (pintype "passive"))
      (node (ref "M") (pin "1") (pinfunction "1_1") (pintype "passive"))
      (node (ref "PGDOWN") (pin "1") (pinfunction "1_1") (pintype "passive"))
      (node (ref "U$1") (pin "P$18") (pinfunction "P$18_P$18") (pintype "bidirectional"))
      (node (ref "VOL-DOWN") (pin "3") (pinfunction "2_3") (pintype "passive"))
    )
    (net (code "19") (name "/19") (class "Default")
      (node (ref "1") (pin "1") (pinfunction "1_1") (pintype "passive"))
      (node (ref "3") (pin "1") (pinfunction "1_1") (pintype "passive"))
      (node (ref "ENTER_1") (pin "1") (pinfunction "1_1") (pintype "passive"))
      (node (ref "ENTER_2") (pin "1") (pinfunction "1_1") (pintype "passive"))
      (node (ref "G") (pin "1") (pinfunction "1_1") (pintype "passive"))
      (node (ref "L-ALT") (pin "1") (pinfunction "1_1") (pintype "passive"))
      (node (ref "MUTE") (pin "3") (pinfunction "2_3") (pintype "passive"))
      (node (ref "PGUP") (pin "1") (pinfunction "1_1") (pintype "passive"))
      (node (ref "U$1") (pin "P$19") (pinfunction "P$19_P$19") (pintype "bidirectional"))
      (node (ref "X") (pin "1") (pinfunction "1_1") (pintype "passive"))
    )
    (net (code "20") (name "/20") (class "Default")
      (node (ref "DOT") (pin "1") (pinfunction "1_1") (pintype "passive"))
      (node (ref "F10") (pin "1") (pinfunction "1_1") (pintype "passive"))
      (node (ref "F12") (pin "1") (pinfunction "1_1") (pintype "passive"))
      (node (ref "F9") (pin "1") (pinfunction "1_1") (pintype "passive"))
      (node (ref "PLAY") (pin "3") (pinfunction "2_3") (pintype "passive"))
      (node (ref "QUOTE") (pin "1") (pinfunction "1_1") (pintype "passive"))
      (node (ref "R-ALT") (pin "3") (pinfunction "2_3") (pintype "passive"))
      (node (ref "U") (pin "1") (pinfunction "1_1") (pintype "passive"))
      (node (ref "U$1") (pin "P$20") (pinfunction "P$20_P$20") (pintype "bidirectional"))
    )
    (net (code "21") (name "/21") (class "Default")
      (node (ref "6") (pin "1") (pinfunction "1_1") (pintype "passive"))
      (node (ref "8") (pin "1") (pinfunction "1_1") (pintype "passive"))
      (node (ref "ESC") (pin "1") (pinfunction "1_1") (pintype "passive"))
      (node (ref "F2") (pin "1") (pinfunction "1_1") (pintype "passive"))
      (node (ref "F3") (pin "1") (pinfunction "1_1") (pintype "passive"))
      (node (ref "L-CTRL") (pin "3") (pinfunction "2_3") (pintype "passive"))
      (node (ref "MAIL") (pin "1") (pinfunction "1_1") (pintype "passive"))
      (node (ref "POWER") (pin "3") (pinfunction "2_3") (pintype "passive"))
      (node (ref "SPACE_1") (pin "1") (pinfunction "1_1") (pintype "passive"))
      (node (ref "SPACE_2") (pin "1") (pinfunction "1_1") (pintype "passive"))
      (node (ref "U$1") (pin "P$21") (pinfunction "P$21_P$21") (pintype "bidirectional"))
      (node (ref "Z") (pin "1") (pinfunction "1_1") (pintype "passive"))
    )
    (net (code "22") (name "/22") (class "Default")
      (node (ref "CALC") (pin "1") (pinfunction "1_1") (pintype "passive"))
      (node (ref "CAPS") (pin "3") (pinfunction "2_3") (pintype "passive"))
      (node (ref "END") (pin "1") (pinfunction "1_1") (pintype "passive"))
      (node (ref "L-ALT") (pin "3") (pinfunction "2_3") (pintype "passive"))
      (node (ref "PIPE") (pin "3") (pinfunction "2_3") (pintype "passive"))
      (node (ref "POWER") (pin "1") (pinfunction "1_1") (pintype "passive"))
      (node (ref "R-ALT") (pin "1") (pinfunction "1_1") (pintype "passive"))
      (node (ref "S-HOME") (pin "1") (pinfunction "1_1") (pintype "passive"))
      (node (ref "U$1") (pin "P$22") (pinfunction "P$22_P$22") (pintype "bidirectional"))
    )
    (net (code "23") (name "/23") (class "Default")
      (node (ref "0") (pin "1") (pinfunction "1_1") (pintype "passive"))
      (node (ref "L-CTRL") (pin "1") (pinfunction "1_1") (pintype "passive"))
      (node (ref "MUTE") (pin "1") (pinfunction "1_1") (pintype "passive"))
      (node (ref "R-CTRL") (pin "1") (pinfunction "1_1") (pintype "passive"))
      (node (ref "U$1") (pin "P$23") (pinfunction "P$23_P$23") (pintype "bidirectional"))
      (node (ref "VOL-DOWN") (pin "1") (pinfunction "1_1") (pintype "passive"))
      (node (ref "VOL-UP") (pin "1") (pinfunction "1_1") (pintype "passive"))
    )
    (net (code "24") (name "/24") (class "Default")
      (node (ref "2") (pin "1") (pinfunction "1_1") (pintype "passive"))
      (node (ref "PLAY") (pin "1") (pinfunction "1_1") (pintype "passive"))
      (node (ref "U$1") (pin "P$24") (pinfunction "P$24_P$24") (pintype "bidirectional"))
      (node (ref "WIN") (pin "1") (pinfunction "1_1") (pintype "passive"))
    )
  )
)
